# twip-mb4.net
KiCad netlist of a schematic drawn in EAGLE
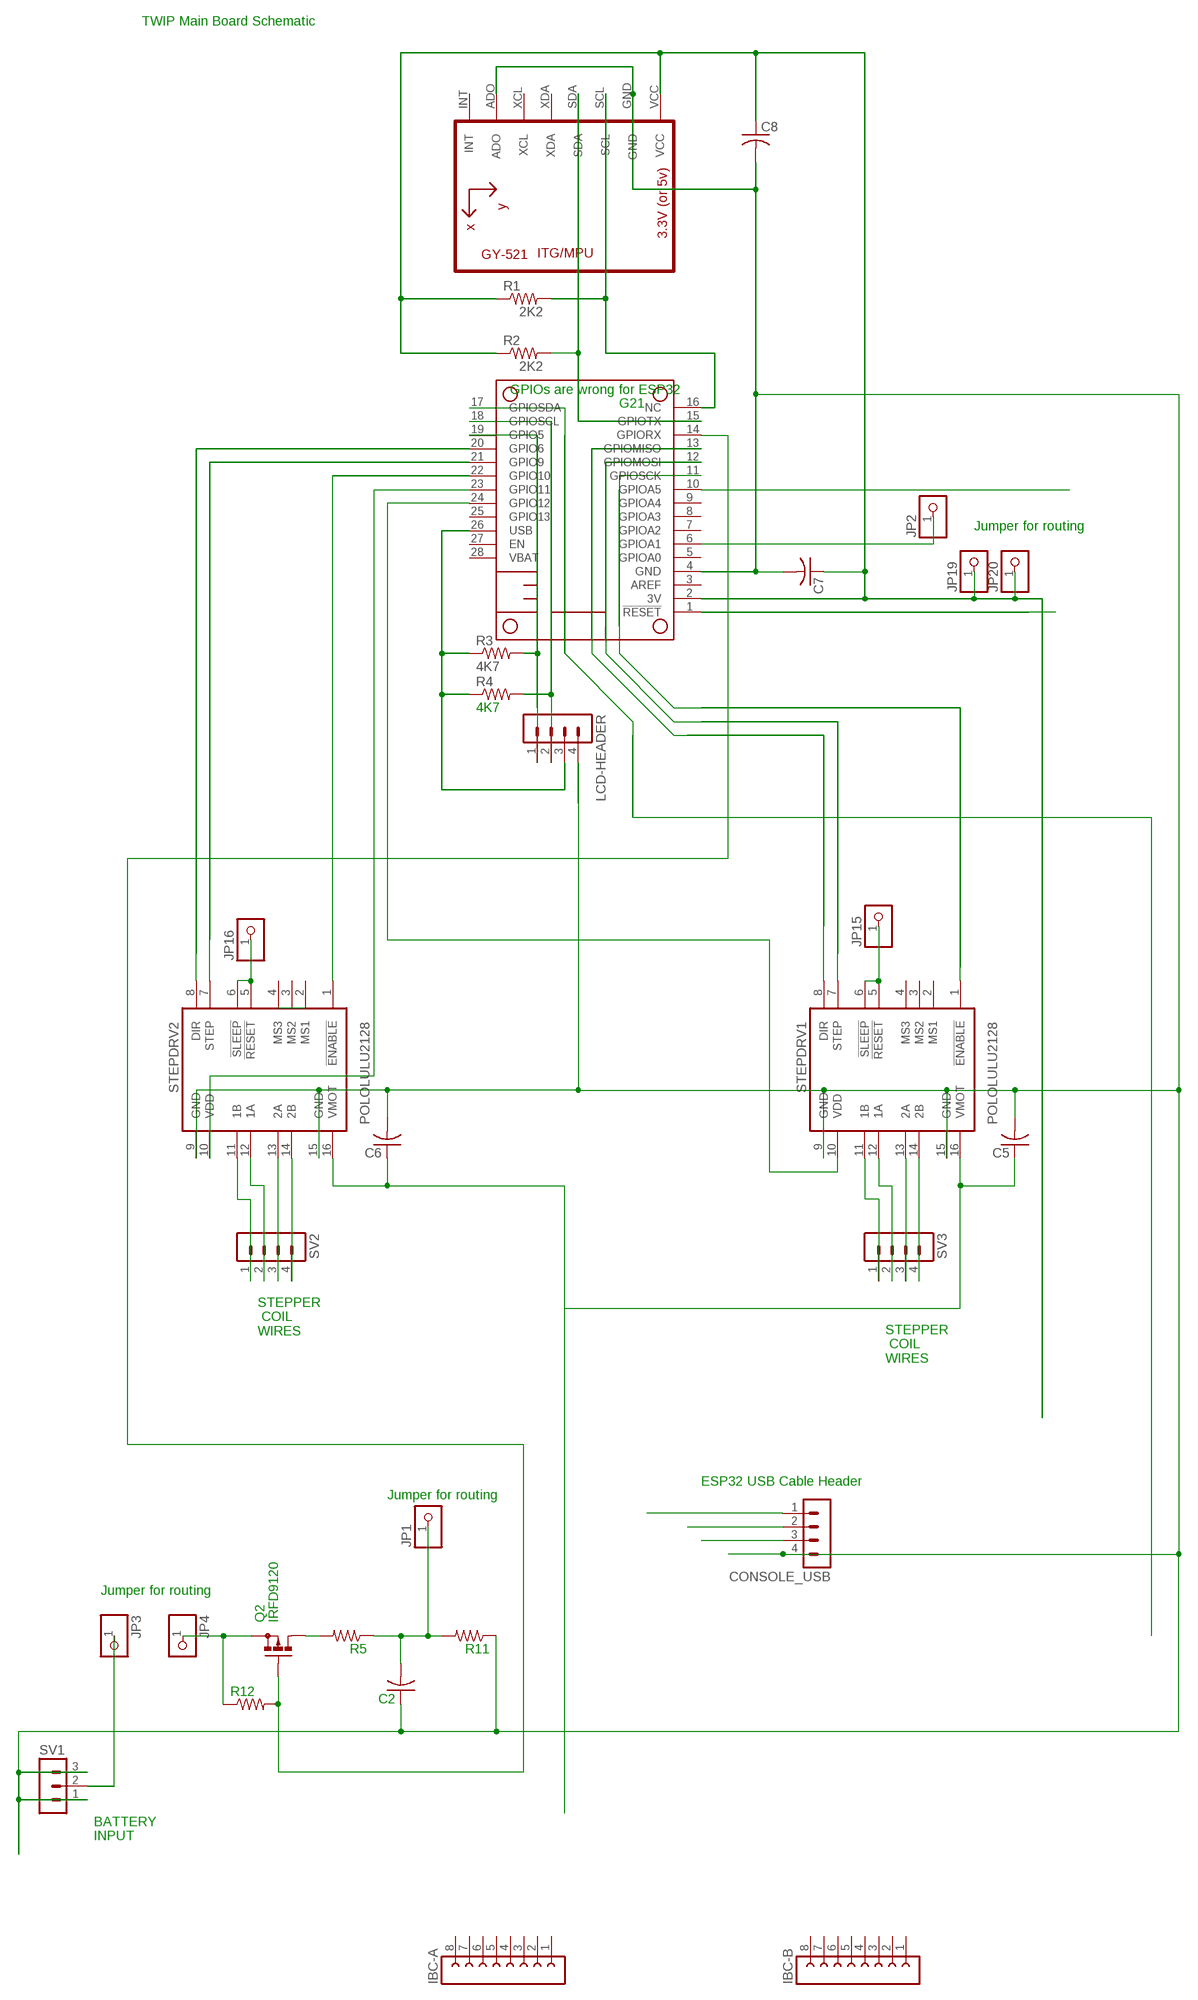
[diagram p0: schematic, sheet 1]

(export (version "E")
  (design (tool "Eeschema 10.0.6"))
  (components
    (comp (ref "C2")
      (value "C-US050-025X075")
      (footprint "eagle-import:C050-025X075")
      (libsource (lib "eagle-import") (part "C-US050-025X075"))
    )
    (comp (ref "C5")
      (value "C-US050-024X044")
      (footprint "eagle-import:C050-024X044")
      (libsource (lib "eagle-import") (part "C-US050-024X044"))
    )
    (comp (ref "C6")
      (value "C-US050-024X044")
      (footprint "eagle-import:C050-024X044")
      (libsource (lib "eagle-import") (part "C-US050-024X044"))
    )
    (comp (ref "C7")
      (value "C-US050-024X044")
      (footprint "eagle-import:C050-024X044")
      (libsource (lib "eagle-import") (part "C-US050-024X044"))
    )
    (comp (ref "C8")
      (value "C-US050-024X044")
      (footprint "eagle-import:C050-024X044")
      (libsource (lib "eagle-import") (part "C-US050-024X044"))
    )
    (comp (ref "CONSOLE_USB")
      (value "MA04-1")
      (footprint "eagle-import:MA04-1")
      (libsource (lib "eagle-import") (part "MA04-1"))
    )
    (comp (ref "IBC-A")
      (value "FE08-1")
      (footprint "eagle-import:FE08")
      (libsource (lib "eagle-import") (part "FE08-1"))
    )
    (comp (ref "IBC-B")
      (value "FE08-1")
      (footprint "eagle-import:FE08")
      (libsource (lib "eagle-import") (part "FE08-1"))
    )
    (comp (ref "JP1")
      (value "PINHD-1X1")
      (footprint "eagle-import:1X01")
      (libsource (lib "eagle-import") (part "PINHD-1X1"))
    )
    (comp (ref "JP2")
      (value "PINHD-1X1")
      (footprint "eagle-import:1X01")
      (libsource (lib "eagle-import") (part "PINHD-1X1"))
    )
    (comp (ref "JP3")
      (value "PINHD-1X1")
      (footprint "eagle-import:1X01")
      (libsource (lib "eagle-import") (part "PINHD-1X1"))
    )
    (comp (ref "JP4")
      (value "PINHD-1X1")
      (footprint "eagle-import:1X01")
      (libsource (lib "eagle-import") (part "PINHD-1X1"))
    )
    (comp (ref "JP15")
      (value "PINHD-1X1")
      (footprint "eagle-import:1X01")
      (libsource (lib "eagle-import") (part "PINHD-1X1"))
    )
    (comp (ref "JP16")
      (value "PINHD-1X1")
      (footprint "eagle-import:1X01")
      (libsource (lib "eagle-import") (part "PINHD-1X1"))
    )
    (comp (ref "JP19")
      (value "PINHD-1X1")
      (footprint "eagle-import:1X01")
      (libsource (lib "eagle-import") (part "PINHD-1X1"))
    )
    (comp (ref "JP20")
      (value "PINHD-1X1")
      (footprint "eagle-import:1X01")
      (libsource (lib "eagle-import") (part "PINHD-1X1"))
    )
    (comp (ref "LCD-HEADER")
      (value "MA04-1")
      (footprint "eagle-import:MA04-1")
      (libsource (lib "eagle-import") (part "MA04-1"))
    )
    (comp (ref "MS2")
      (value "FEATHERWING_NOHOLES")
      (footprint "eagle-import:FEATHERWING_NOHOLES")
      (libsource (lib "eagle-import") (part "FEATHERWING_NOHOLES"))
    )
    (comp (ref "Q2")
      (value "IRFD9120")
      (footprint "eagle-import:C370-01")
      (libsource (lib "eagle-import") (part "IRFD9120"))
    )
    (comp (ref "R1")
      (value "2K2")
      (footprint "eagle-import:0309_12")
      (libsource (lib "eagle-import") (part "resistor_348_R-US_0309/12"))
    )
    (comp (ref "R2")
      (value "2K2")
      (footprint "eagle-import:0309_12")
      (libsource (lib "eagle-import") (part "resistor_348_R-US_0309/12"))
    )
    (comp (ref "R3")
      (value "4K7")
      (footprint "eagle-import:0309_12")
      (libsource (lib "eagle-import") (part "resistor_348_R-US_0309/12"))
    )
    (comp (ref "R4")
      (value "4K7")
      (footprint "eagle-import:0309_12")
      (libsource (lib "eagle-import") (part "resistor_348_R-US_0309/12"))
    )
    (comp (ref "R5")
      (value "R-US_0207/10")
      (footprint "eagle-import:0207_10")
      (libsource (lib "eagle-import") (part "R-US_0207/10"))
    )
    (comp (ref "R11")
      (value "R-US_0207/10")
      (footprint "eagle-import:0207_10")
      (libsource (lib "eagle-import") (part "R-US_0207/10"))
    )
    (comp (ref "R12")
      (value "R-US_0207/10")
      (footprint "eagle-import:0207_10")
      (libsource (lib "eagle-import") (part "R-US_0207/10"))
    )
    (comp (ref "STEPDRV1")
      (value "POLOLULU2128")
      (footprint "eagle-import:POLOLULU2128")
      (libsource (lib "eagle-import") (part "POLOLULU2128"))
    )
    (comp (ref "STEPDRV2")
      (value "POLOLULU2128")
      (footprint "eagle-import:POLOLULU2128")
      (libsource (lib "eagle-import") (part "POLOLULU2128"))
    )
    (comp (ref "SV1")
      (value "MA03-1")
      (footprint "eagle-import:MA03-1")
      (libsource (lib "eagle-import") (part "MA03-1"))
    )
    (comp (ref "SV2")
      (value "MA04-1")
      (footprint "eagle-import:MA04-1")
      (libsource (lib "eagle-import") (part "MA04-1"))
    )
    (comp (ref "SV3")
      (value "MA04-1")
      (footprint "eagle-import:MA04-1")
      (libsource (lib "eagle-import") (part "MA04-1"))
    )
    (comp (ref "U1")
      (value "GY-521MPU6050")
      (footprint "eagle-import:GY-521")
      (libsource (lib "eagle-import") (part "GY-521MPU6050"))
    )
  )
  (nets
    (net (code "1") (name "/VBAT") (class "Default")
      (node (ref "MS2") (pin "28") (pinfunction "VBAT_28") (pintype "power_in"))
    )
    (net (code "2") (name "Net-(C2-Pad2)") (class "Default")
      (node (ref "C2") (pin "2") (pinfunction "2_2") (pintype "passive"))
      (node (ref "JP1") (pin "1") (pinfunction "1_1") (pintype "passive"))
      (node (ref "R11") (pin "2") (pinfunction "2_2") (pintype "passive"))
      (node (ref "R5") (pin "1") (pinfunction "1_1") (pintype "passive"))
    )
    (net (code "3") (name "Net-(JP3-Pad1)") (class "Default")
      (node (ref "JP3") (pin "1") (pinfunction "1_1") (pintype "passive"))
      (node (ref "SV1") (pin "2") (pinfunction "2_2") (pintype "passive"))
    )
    (net (code "4") (name "Net-(JP4-Pad1)") (class "Default")
      (node (ref "JP4") (pin "1") (pinfunction "1_1") (pintype "passive"))
      (node (ref "Q2") (pin "S") (pinfunction "S_S") (pintype "passive"))
      (node (ref "R12") (pin "1") (pinfunction "1_1") (pintype "passive"))
    )
    (net (code "5") (name "Net-(MS2-3V)") (class "Default")
      (node (ref "C7") (pin "1") (pinfunction "1_1") (pintype "passive"))
      (node (ref "C8") (pin "1") (pinfunction "1_1") (pintype "passive"))
      (node (ref "JP19") (pin "1") (pinfunction "1_1") (pintype "passive"))
      (node (ref "JP20") (pin "1") (pinfunction "1_1") (pintype "passive"))
      (node (ref "MS2") (pin "2") (pinfunction "3V_2") (pintype "power_in"))
      (node (ref "R1") (pin "1") (pinfunction "1_1") (pintype "passive"))
      (node (ref "R2") (pin "1") (pinfunction "1_1") (pintype "passive"))
      (node (ref "U1") (pin "VCC") (pinfunction "VCC_VCC") (pintype "bidirectional"))
    )
    (net (code "6") (name "Net-(MS2-GND)") (class "Default")
      (node (ref "C2") (pin "1") (pinfunction "1_1") (pintype "passive"))
      (node (ref "C5") (pin "2") (pinfunction "2_2") (pintype "passive"))
      (node (ref "C6") (pin "2") (pinfunction "2_2") (pintype "passive"))
      (node (ref "C7") (pin "2") (pinfunction "2_2") (pintype "passive"))
      (node (ref "C8") (pin "2") (pinfunction "2_2") (pintype "passive"))
      (node (ref "CONSOLE_USB") (pin "4") (pinfunction "4_4") (pintype "passive"))
      (node (ref "LCD-HEADER") (pin "4") (pinfunction "4_4") (pintype "passive"))
      (node (ref "MS2") (pin "4") (pinfunction "GND_4") (pintype "power_in"))
      (node (ref "R11") (pin "1") (pinfunction "1_1") (pintype "passive"))
      (node (ref "STEPDRV1") (pin "15") (pinfunction "GND_15") (pintype "power_in"))
      (node (ref "STEPDRV1") (pin "9") (pinfunction "GND_9") (pintype "power_in"))
      (node (ref "STEPDRV2") (pin "15") (pinfunction "GND_15") (pintype "power_in"))
      (node (ref "STEPDRV2") (pin "9") (pinfunction "GND_9") (pintype "power_in"))
      (node (ref "SV1") (pin "1") (pinfunction "1_1") (pintype "passive"))
      (node (ref "SV1") (pin "3") (pinfunction "3_3") (pintype "passive"))
      (node (ref "U1") (pin "ADO") (pinfunction "ADO_ADO") (pintype "bidirectional"))
      (node (ref "U1") (pin "GND") (pinfunction "GND_GND") (pintype "bidirectional"))
    )
    (net (code "7") (name "Net-(MS2-GPIO5)") (class "Default")
      (node (ref "LCD-HEADER") (pin "1") (pinfunction "1_1") (pintype "passive"))
      (node (ref "MS2") (pin "19") (pinfunction "GPIO5_19") (pintype "bidirectional"))
      (node (ref "R3") (pin "2") (pinfunction "2_2") (pintype "passive"))
    )
    (net (code "8") (name "Net-(MS2-GPIO6)") (class "Default")
      (node (ref "MS2") (pin "20") (pinfunction "GPIO6_20") (pintype "bidirectional"))
      (node (ref "STEPDRV2") (pin "8") (pinfunction "DIR_8") (pintype "input"))
    )
    (net (code "9") (name "Net-(MS2-GPIO9)") (class "Default")
      (node (ref "MS2") (pin "21") (pinfunction "GPIO9_21") (pintype "bidirectional"))
      (node (ref "STEPDRV2") (pin "7") (pinfunction "STEP_7") (pintype "input"))
    )
    (net (code "10") (name "Net-(MS2-GPIO10)") (class "Default")
      (node (ref "MS2") (pin "22") (pinfunction "GPIO10_22") (pintype "bidirectional"))
      (node (ref "STEPDRV2") (pin "1") (pinfunction "~{ENABLE}_1") (pintype "input"))
    )
    (net (code "11") (name "Net-(MS2-GPIO11)") (class "Default")
      (node (ref "MS2") (pin "23") (pinfunction "GPIO11_23") (pintype "bidirectional"))
      (node (ref "STEPDRV2") (pin "10") (pinfunction "VDD_10") (pintype "power_in"))
    )
    (net (code "12") (name "Net-(MS2-GPIO12)") (class "Default")
      (node (ref "MS2") (pin "24") (pinfunction "GPIO12_24") (pintype "bidirectional"))
      (node (ref "STEPDRV1") (pin "10") (pinfunction "VDD_10") (pintype "power_in"))
    )
    (net (code "13") (name "Net-(MS2-GPIOA1)") (class "Default")
      (node (ref "JP2") (pin "1") (pinfunction "1_1") (pintype "passive"))
      (node (ref "MS2") (pin "6") (pinfunction "GPIOA1_6") (pintype "bidirectional"))
    )
    (net (code "14") (name "Net-(MS2-GPIOMISO)") (class "Default")
      (node (ref "MS2") (pin "13") (pinfunction "GPIOMISO_13") (pintype "bidirectional"))
      (node (ref "STEPDRV1") (pin "8") (pinfunction "DIR_8") (pintype "input"))
    )
    (net (code "15") (name "Net-(MS2-GPIOMOSI)") (class "Default")
      (node (ref "MS2") (pin "12") (pinfunction "GPIOMOSI_12") (pintype "bidirectional"))
      (node (ref "STEPDRV1") (pin "7") (pinfunction "STEP_7") (pintype "input"))
    )
    (net (code "16") (name "Net-(MS2-GPIORX)") (class "Default")
      (node (ref "MS2") (pin "14") (pinfunction "GPIORX_14") (pintype "bidirectional"))
      (node (ref "Q2") (pin "G") (pinfunction "G_G") (pintype "passive"))
      (node (ref "R12") (pin "2") (pinfunction "2_2") (pintype "passive"))
    )
    (net (code "17") (name "Net-(MS2-GPIOSCK)") (class "Default")
      (node (ref "MS2") (pin "11") (pinfunction "GPIOSCK_11") (pintype "bidirectional"))
      (node (ref "STEPDRV1") (pin "1") (pinfunction "~{ENABLE}_1") (pintype "input"))
    )
    (net (code "18") (name "Net-(MS2-GPIOSCL)") (class "Default")
      (node (ref "LCD-HEADER") (pin "2") (pinfunction "2_2") (pintype "passive"))
      (node (ref "MS2") (pin "18") (pinfunction "GPIOSCL_18") (pintype "bidirectional"))
      (node (ref "R4") (pin "2") (pinfunction "2_2") (pintype "passive"))
    )
    (net (code "19") (name "Net-(MS2-GPIOTX)") (class "Default")
      (node (ref "MS2") (pin "15") (pinfunction "GPIOTX_15") (pintype "bidirectional"))
      (node (ref "R2") (pin "2") (pinfunction "2_2") (pintype "passive"))
      (node (ref "U1") (pin "SDA") (pinfunction "SDA_SDA") (pintype "bidirectional"))
    )
    (net (code "20") (name "Net-(MS2-NC)") (class "Default")
      (node (ref "MS2") (pin "16") (pinfunction "NC_16") (pintype "passive"))
      (node (ref "R1") (pin "2") (pinfunction "2_2") (pintype "passive"))
      (node (ref "U1") (pin "SCL") (pinfunction "SCL_SCL") (pintype "bidirectional"))
    )
    (net (code "21") (name "Net-(MS2-USB)") (class "Default")
      (node (ref "LCD-HEADER") (pin "3") (pinfunction "3_3") (pintype "passive"))
      (node (ref "MS2") (pin "26") (pinfunction "USB_26") (pintype "power_in"))
      (node (ref "R3") (pin "1") (pinfunction "1_1") (pintype "passive"))
      (node (ref "R4") (pin "1") (pinfunction "1_1") (pintype "passive"))
    )
    (net (code "22") (name "Net-(Q2-D-PadD1)") (class "Default")
      (node (ref "Q2") (pin "D") (pinfunction "D_D") (pintype "passive"))
      (node (ref "Q2") (pin "D1") (pinfunction "D_D1") (pintype "passive"))
      (node (ref "R5") (pin "2") (pinfunction "2_2") (pintype "passive"))
    )
    (net (code "23") (name "Net-(STEPDRV1-1A)") (class "Default")
      (node (ref "STEPDRV1") (pin "12") (pinfunction "1A_12") (pintype "output"))
      (node (ref "SV3") (pin "2") (pinfunction "2_2") (pintype "passive"))
    )
    (net (code "24") (name "Net-(STEPDRV1-1B)") (class "Default")
      (node (ref "STEPDRV1") (pin "11") (pinfunction "1B_11") (pintype "output"))
      (node (ref "SV3") (pin "1") (pinfunction "1_1") (pintype "passive"))
    )
    (net (code "25") (name "Net-(STEPDRV1-2A)") (class "Default")
      (node (ref "STEPDRV1") (pin "13") (pinfunction "2A_13") (pintype "output"))
      (node (ref "SV3") (pin "3") (pinfunction "3_3") (pintype "passive"))
    )
    (net (code "26") (name "Net-(STEPDRV1-2B)") (class "Default")
      (node (ref "STEPDRV1") (pin "14") (pinfunction "2B_14") (pintype "output"))
      (node (ref "SV3") (pin "4") (pinfunction "4_4") (pintype "passive"))
    )
    (net (code "27") (name "Net-(STEPDRV1-VMOT)") (class "Default")
      (node (ref "C5") (pin "1") (pinfunction "1_1") (pintype "passive"))
      (node (ref "STEPDRV1") (pin "16") (pinfunction "VMOT_16") (pintype "power_in"))
    )
    (net (code "28") (name "Net-(STEPDRV1-~{RESET})") (class "Default")
      (node (ref "JP15") (pin "1") (pinfunction "1_1") (pintype "passive"))
      (node (ref "STEPDRV1") (pin "5") (pinfunction "~{RESET}_5") (pintype "input"))
      (node (ref "STEPDRV1") (pin "6") (pinfunction "~{SLEEP}_6") (pintype "input"))
    )
    (net (code "29") (name "Net-(STEPDRV2-1A)") (class "Default")
      (node (ref "STEPDRV2") (pin "12") (pinfunction "1A_12") (pintype "output"))
      (node (ref "SV2") (pin "2") (pinfunction "2_2") (pintype "passive"))
    )
    (net (code "30") (name "Net-(STEPDRV2-1B)") (class "Default")
      (node (ref "STEPDRV2") (pin "11") (pinfunction "1B_11") (pintype "output"))
      (node (ref "SV2") (pin "1") (pinfunction "1_1") (pintype "passive"))
    )
    (net (code "31") (name "Net-(STEPDRV2-2A)") (class "Default")
      (node (ref "STEPDRV2") (pin "13") (pinfunction "2A_13") (pintype "output"))
      (node (ref "SV2") (pin "3") (pinfunction "3_3") (pintype "passive"))
    )
    (net (code "32") (name "Net-(STEPDRV2-2B)") (class "Default")
      (node (ref "STEPDRV2") (pin "14") (pinfunction "2B_14") (pintype "output"))
      (node (ref "SV2") (pin "4") (pinfunction "4_4") (pintype "passive"))
    )
    (net (code "33") (name "Net-(STEPDRV2-VMOT)") (class "Default")
      (node (ref "C6") (pin "1") (pinfunction "1_1") (pintype "passive"))
      (node (ref "STEPDRV2") (pin "16") (pinfunction "VMOT_16") (pintype "power_in"))
    )
    (net (code "34") (name "Net-(STEPDRV2-~{RESET})") (class "Default")
      (node (ref "JP16") (pin "1") (pinfunction "1_1") (pintype "passive"))
      (node (ref "STEPDRV2") (pin "5") (pinfunction "~{RESET}_5") (pintype "input"))
      (node (ref "STEPDRV2") (pin "6") (pinfunction "~{SLEEP}_6") (pintype "input"))
    )
    (net (code "35") (name "unconnected-(CONSOLE_USB-Pad1)") (class "Default")
      (node (ref "CONSOLE_USB") (pin "1") (pinfunction "1_1") (pintype "passive"))
    )
    (net (code "36") (name "unconnected-(CONSOLE_USB-Pad2)") (class "Default")
      (node (ref "CONSOLE_USB") (pin "2") (pinfunction "2_2") (pintype "passive"))
    )
    (net (code "37") (name "unconnected-(CONSOLE_USB-Pad3)") (class "Default")
      (node (ref "CONSOLE_USB") (pin "3") (pinfunction "3_3") (pintype "passive"))
    )
    (net (code "38") (name "unconnected-(IBC-A-Pad1)") (class "Default")
      (node (ref "IBC-A") (pin "1") (pinfunction "1_1") (pintype "passive"))
    )
    (net (code "39") (name "unconnected-(IBC-A-Pad2)") (class "Default")
      (node (ref "IBC-A") (pin "2") (pinfunction "2_2") (pintype "passive"))
    )
    (net (code "40") (name "unconnected-(IBC-A-Pad3)") (class "Default")
      (node (ref "IBC-A") (pin "3") (pinfunction "3_3") (pintype "passive"))
    )
    (net (code "41") (name "unconnected-(IBC-A-Pad4)") (class "Default")
      (node (ref "IBC-A") (pin "4") (pinfunction "4_4") (pintype "passive"))
    )
    (net (code "42") (name "unconnected-(IBC-A-Pad5)") (class "Default")
      (node (ref "IBC-A") (pin "5") (pinfunction "5_5") (pintype "passive"))
    )
    (net (code "43") (name "unconnected-(IBC-A-Pad6)") (class "Default")
      (node (ref "IBC-A") (pin "6") (pinfunction "6_6") (pintype "passive"))
    )
    (net (code "44") (name "unconnected-(IBC-A-Pad7)") (class "Default")
      (node (ref "IBC-A") (pin "7") (pinfunction "7_7") (pintype "passive"))
    )
    (net (code "45") (name "unconnected-(IBC-A-Pad8)") (class "Default")
      (node (ref "IBC-A") (pin "8") (pinfunction "8_8") (pintype "passive"))
    )
    (net (code "46") (name "unconnected-(IBC-B-Pad1)") (class "Default")
      (node (ref "IBC-B") (pin "1") (pinfunction "1_1") (pintype "passive"))
    )
    (net (code "47") (name "unconnected-(IBC-B-Pad2)") (class "Default")
      (node (ref "IBC-B") (pin "2") (pinfunction "2_2") (pintype "passive"))
    )
    (net (code "48") (name "unconnected-(IBC-B-Pad3)") (class "Default")
      (node (ref "IBC-B") (pin "3") (pinfunction "3_3") (pintype "passive"))
    )
    (net (code "49") (name "unconnected-(IBC-B-Pad4)") (class "Default")
      (node (ref "IBC-B") (pin "4") (pinfunction "4_4") (pintype "passive"))
    )
    (net (code "50") (name "unconnected-(IBC-B-Pad5)") (class "Default")
      (node (ref "IBC-B") (pin "5") (pinfunction "5_5") (pintype "passive"))
    )
    (net (code "51") (name "unconnected-(IBC-B-Pad6)") (class "Default")
      (node (ref "IBC-B") (pin "6") (pinfunction "6_6") (pintype "passive"))
    )
    (net (code "52") (name "unconnected-(IBC-B-Pad7)") (class "Default")
      (node (ref "IBC-B") (pin "7") (pinfunction "7_7") (pintype "passive"))
    )
    (net (code "53") (name "unconnected-(IBC-B-Pad8)") (class "Default")
      (node (ref "IBC-B") (pin "8") (pinfunction "8_8") (pintype "passive"))
    )
    (net (code "54") (name "unconnected-(MS2-AREF-Pad3)") (class "Default")
      (node (ref "MS2") (pin "3") (pinfunction "AREF_3") (pintype "passive"))
    )
    (net (code "55") (name "unconnected-(MS2-EN-Pad27)") (class "Default")
      (node (ref "MS2") (pin "27") (pinfunction "EN_27") (pintype "passive"))
    )
    (net (code "56") (name "unconnected-(MS2-GPIO13-Pad25)") (class "Default")
      (node (ref "MS2") (pin "25") (pinfunction "GPIO13_25") (pintype "bidirectional"))
    )
    (net (code "57") (name "unconnected-(MS2-GPIOA0-Pad5)") (class "Default")
      (node (ref "MS2") (pin "5") (pinfunction "GPIOA0_5") (pintype "bidirectional"))
    )
    (net (code "58") (name "unconnected-(MS2-GPIOA2-Pad7)") (class "Default")
      (node (ref "MS2") (pin "7") (pinfunction "GPIOA2_7") (pintype "bidirectional"))
    )
    (net (code "59") (name "unconnected-(MS2-GPIOA3-Pad8)") (class "Default")
      (node (ref "MS2") (pin "8") (pinfunction "GPIOA3_8") (pintype "bidirectional"))
    )
    (net (code "60") (name "unconnected-(MS2-GPIOA4-Pad9)") (class "Default")
      (node (ref "MS2") (pin "9") (pinfunction "GPIOA4_9") (pintype "bidirectional"))
    )
    (net (code "61") (name "unconnected-(MS2-GPIOA5-Pad10)") (class "Default")
      (node (ref "MS2") (pin "10") (pinfunction "GPIOA5_10") (pintype "bidirectional"))
    )
    (net (code "62") (name "unconnected-(MS2-GPIOSDA-Pad17)") (class "Default")
      (node (ref "MS2") (pin "17") (pinfunction "GPIOSDA_17") (pintype "bidirectional"))
    )
    (net (code "63") (name "unconnected-(MS2-~{RESET}-Pad1)") (class "Default")
      (node (ref "MS2") (pin "1") (pinfunction "~{RESET}_1") (pintype "input"))
    )
    (net (code "64") (name "unconnected-(STEPDRV1-MS1-Pad2)") (class "Default")
      (node (ref "STEPDRV1") (pin "2") (pinfunction "MS1_2") (pintype "input"))
    )
    (net (code "65") (name "unconnected-(STEPDRV1-MS2-Pad3)") (class "Default")
      (node (ref "STEPDRV1") (pin "3") (pinfunction "MS2_3") (pintype "input"))
    )
    (net (code "66") (name "unconnected-(STEPDRV1-MS3-Pad4)") (class "Default")
      (node (ref "STEPDRV1") (pin "4") (pinfunction "MS3_4") (pintype "input"))
    )
    (net (code "67") (name "unconnected-(STEPDRV2-MS1-Pad2)") (class "Default")
      (node (ref "STEPDRV2") (pin "2") (pinfunction "MS1_2") (pintype "input"))
    )
    (net (code "68") (name "unconnected-(STEPDRV2-MS2-Pad3)") (class "Default")
      (node (ref "STEPDRV2") (pin "3") (pinfunction "MS2_3") (pintype "input"))
    )
    (net (code "69") (name "unconnected-(STEPDRV2-MS3-Pad4)") (class "Default")
      (node (ref "STEPDRV2") (pin "4") (pinfunction "MS3_4") (pintype "input"))
    )
    (net (code "70") (name "unconnected-(U1-PadINT)") (class "Default")
      (node (ref "U1") (pin "INT") (pinfunction "INT_INT") (pintype "bidirectional"))
    )
    (net (code "71") (name "unconnected-(U1-PadXCL)") (class "Default")
      (node (ref "U1") (pin "XCL") (pinfunction "XCL_XCL") (pintype "bidirectional"))
    )
    (net (code "72") (name "unconnected-(U1-PadXDA)") (class "Default")
      (node (ref "U1") (pin "XDA") (pinfunction "XDA_XDA") (pintype "bidirectional"))
    )
  )
)
